# Battery_Monitoring.net
KiCad netlist of a schematic drawn in Altium Designer
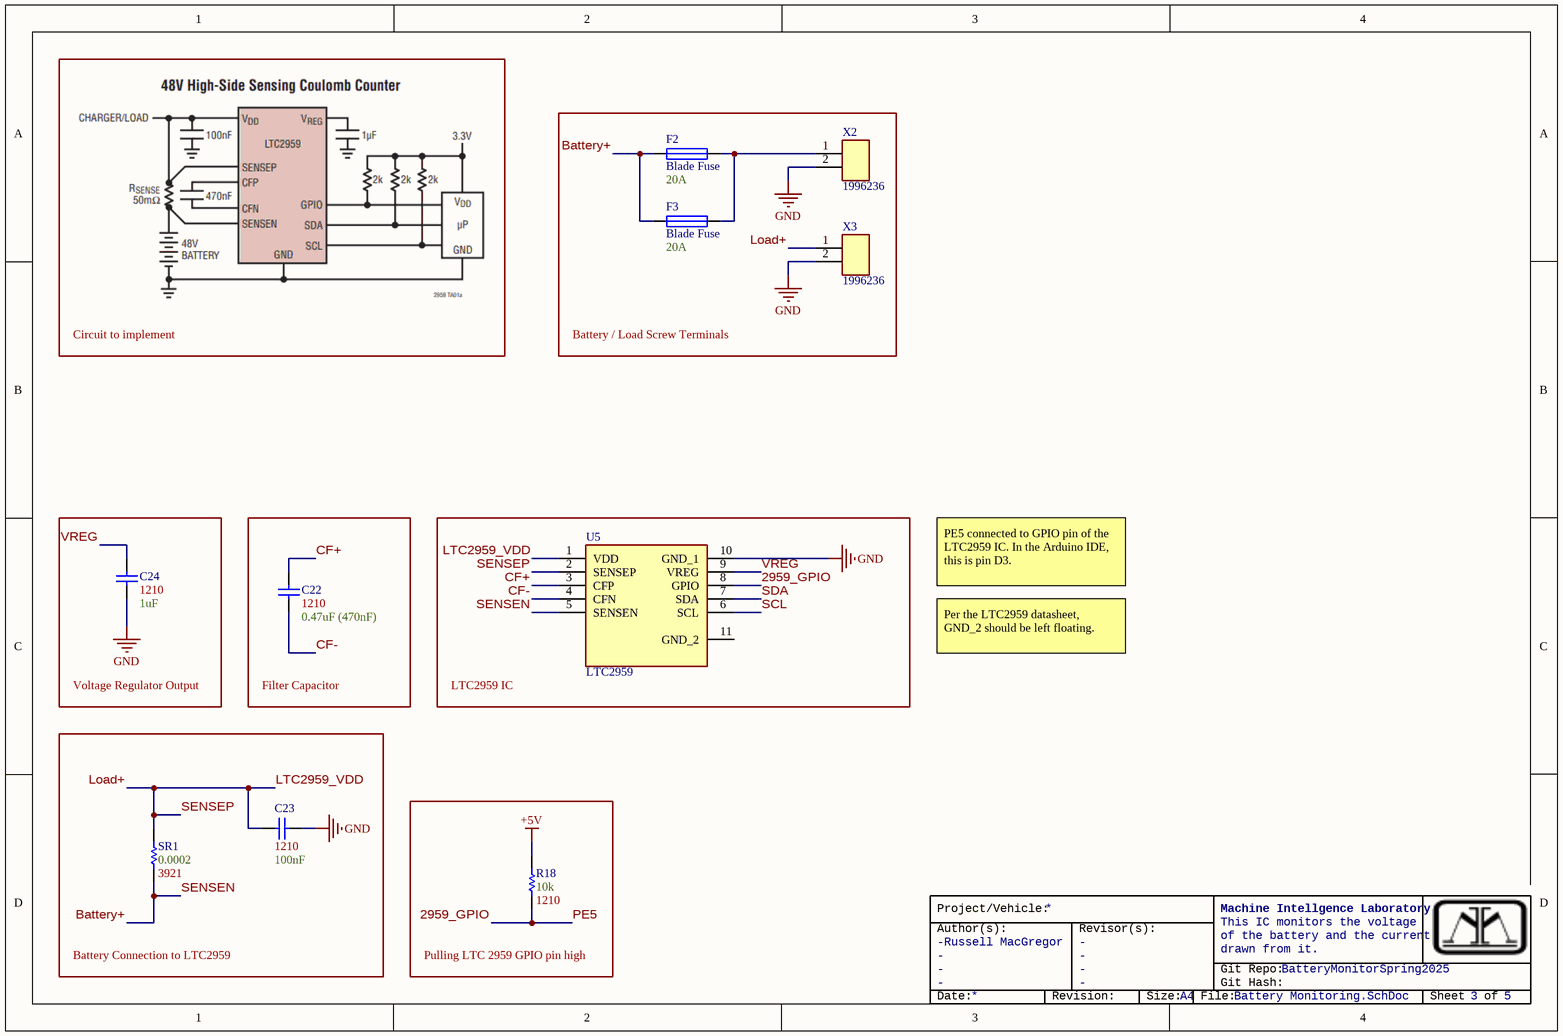
[diagram p0: Battery Monitoring.SchDoc]

(export (version "E")
  (design (tool "Eeschema 10.0.6"))
  (components
    (comp (ref "C22")
      (value "SMD Cap - Nonpolarized")
      (footprint "SMD Capacitor [1210]")
      (fields
        (field (name "MOUSER PART #") "80-C1210C474K1RAUTO")
        (field (name "SIZE PACKAGE") "1210")
        (field (name "CAPACITANCE") "0.47uF (470nF)")
      )
      (libsource (lib "RADM Components") (part "SMD Cap - Nonpolarized"))
    )
    (comp (ref "C23")
      (value "SMD Cap - Nonpolarized")
      (footprint "SMD Capacitor [1210]")
      (fields
        (field (name "MOUSER PART #") "581-12107C104KAT2A")
        (field (name "SIZE PACKAGE") "1210")
        (field (name "CAPACITANCE") "100nF")
      )
      (libsource (lib "RADM Components") (part "SMD Cap - Nonpolarized"))
    )
    (comp (ref "C24")
      (value "SMD Cap - Nonpolarized")
      (footprint "SMD Capacitor [1210]")
      (fields
        (field (name "MOUSER PART #") "80-C1210X105K5RAUTO")
        (field (name "SIZE PACKAGE") "1210")
        (field (name "CAPACITANCE") "1uF")
      )
      (libsource (lib "RADM Components") (part "SMD Cap - Nonpolarized"))
    )
    (comp (ref "F2")
      (value "Blade Fuse")
      (footprint "Blade Fuse [2]")
      (description "Standard Fuse Socket")
      (fields (field (name "MOUSER PART #") "576-178.6165.0002") (field (name "CAPACITY") "20A"))
      (libsource (lib "RADM Components") (part "Blade Fuse"))
    )
    (comp (ref "F3")
      (value "Blade Fuse")
      (footprint "Blade Fuse [2]")
      (description "Standard Fuse Socket")
      (fields (field (name "MOUSER PART #") "576-178.6165.0002") (field (name "CAPACITY") "20A"))
      (libsource (lib "RADM Components") (part "Blade Fuse"))
    )
    (comp (ref "R18")
      (value "SMD Resistor")
      (footprint "SMD Resistor [1210]")
      (description "JLC Part #: C728401\r\n(for 1M Ohm Res)")
      (fields
        (field (name "MOUSER PART #") "71-CRCW121010K0JNAIF")
        (field (name "RESISTANCE") "10k")
        (field (name "SIZE PACKAGE") "1210")
      )
      (libsource (lib "RADM Components") (part "SMD Resistor"))
    )
    (comp (ref "SR1")
      (value "SMD Resistor")
      (footprint "SMD Resistor [3921]")
      (fields
        (field (name "JLC PART #") "C728401")
        (field (name "MOUSER PART #") "71-WSL3921L2000FEA")
        (field (name "RESISTANCE") "0.0002")
        (field (name "SIZE PACKAGE") "3921")
      )
      (libsource (lib "RADM Components") (part "SMD Resistor"))
    )
    (comp (ref "U5")
      (value "LTC2959")
      (footprint "Battery Monitor IC")
      (fields (field (name "MOUSER PART #") "584-LTC2959IDDBTRMPB"))
      (libsource (lib "RADM Components") (part "LTC2959 Battery Monitor IC"))
    )
    (comp (ref "X2")
      (value "1996236")
      (footprint "Screw Terminal [1996236]")
      (fields (field (name "MOUSER PART #") "651-1996236"))
      (libsource (lib "RADM Components") (part "Screw Terminal [1996236]"))
    )
    (comp (ref "X3")
      (value "1996236")
      (footprint "Screw Terminal [1996236]")
      (fields (field (name "MOUSER PART #") "651-1996236"))
      (libsource (lib "RADM Components") (part "Screw Terminal [1996236]"))
    )
  )
  (nets
    (net (code "1") (name "+5V") (class "Default")
      (node (ref "R18") (pin "1") (pinfunction "1_1") (pintype "passive"))
    )
    (net (code "2") (name "/2959_GPIO") (class "Default")
      (node (ref "R18") (pin "2") (pinfunction "2_2") (pintype "passive"))
      (node (ref "U5") (pin "8") (pinfunction "GPIO_8") (pintype "passive"))
    )
    (net (code "3") (name "/Battery+") (class "Default")
      (node (ref "F2") (pin "1") (pinfunction "1_1") (pintype "passive"))
      (node (ref "F3") (pin "1") (pinfunction "1_1") (pintype "passive"))
      (node (ref "SR1") (pin "1") (pinfunction "1_1") (pintype "passive"))
      (node (ref "U5") (pin "5") (pinfunction "SENSEN_5") (pintype "passive"))
    )
    (net (code "4") (name "/CF+") (class "Default")
      (node (ref "C22") (pin "1") (pinfunction "1_1") (pintype "passive"))
      (node (ref "U5") (pin "3") (pinfunction "CFP_3") (pintype "passive"))
    )
    (net (code "5") (name "/CF-") (class "Default")
      (node (ref "C22") (pin "2") (pinfunction "2_2") (pintype "passive"))
      (node (ref "U5") (pin "4") (pinfunction "CFN_4") (pintype "passive"))
    )
    (net (code "6") (name "/LTC2959_VDD") (class "Default")
      (node (ref "C23") (pin "2") (pinfunction "2_2") (pintype "passive"))
      (node (ref "SR1") (pin "2") (pinfunction "2_2") (pintype "passive"))
      (node (ref "U5") (pin "1") (pinfunction "VDD_1") (pintype "passive"))
      (node (ref "U5") (pin "2") (pinfunction "SENSEP_2") (pintype "passive"))
      (node (ref "X3") (pin "1") (pintype "passive"))
    )
    (net (code "7") (name "/SCL") (class "Default")
      (node (ref "U5") (pin "6") (pinfunction "SCL_6") (pintype "passive"))
    )
    (net (code "8") (name "/SDA") (class "Default")
      (node (ref "U5") (pin "7") (pinfunction "SDA_7") (pintype "passive"))
    )
    (net (code "9") (name "/VREG") (class "Default")
      (node (ref "C24") (pin "1") (pinfunction "1_1") (pintype "passive"))
      (node (ref "U5") (pin "9") (pinfunction "VREG_9") (pintype "passive"))
    )
    (net (code "10") (name "GND") (class "Default")
      (node (ref "C23") (pin "1") (pinfunction "1_1") (pintype "passive"))
      (node (ref "C24") (pin "2") (pinfunction "2_2") (pintype "passive"))
      (node (ref "U5") (pin "10") (pinfunction "GND_1_10") (pintype "passive"))
      (node (ref "X2") (pin "2") (pinfunction "2_2") (pintype "passive"))
      (node (ref "X3") (pin "2") (pinfunction "2_2") (pintype "passive"))
    )
    (net (code "11") (name "Net-(F2-Pad2)") (class "Default")
      (node (ref "F2") (pin "2") (pinfunction "2_2") (pintype "passive"))
      (node (ref "F3") (pin "2") (pinfunction "2_2") (pintype "passive"))
      (node (ref "X2") (pin "1") (pintype "passive"))
    )
    (net (code "12") (name "unconnected-(U5-GND_2-Pad11)") (class "Default")
      (node (ref "U5") (pin "11") (pinfunction "GND_2_11") (pintype "passive"))
    )
  )
)
